# Pyros.net
KiCad netlist of a schematic drawn in Altium Designer
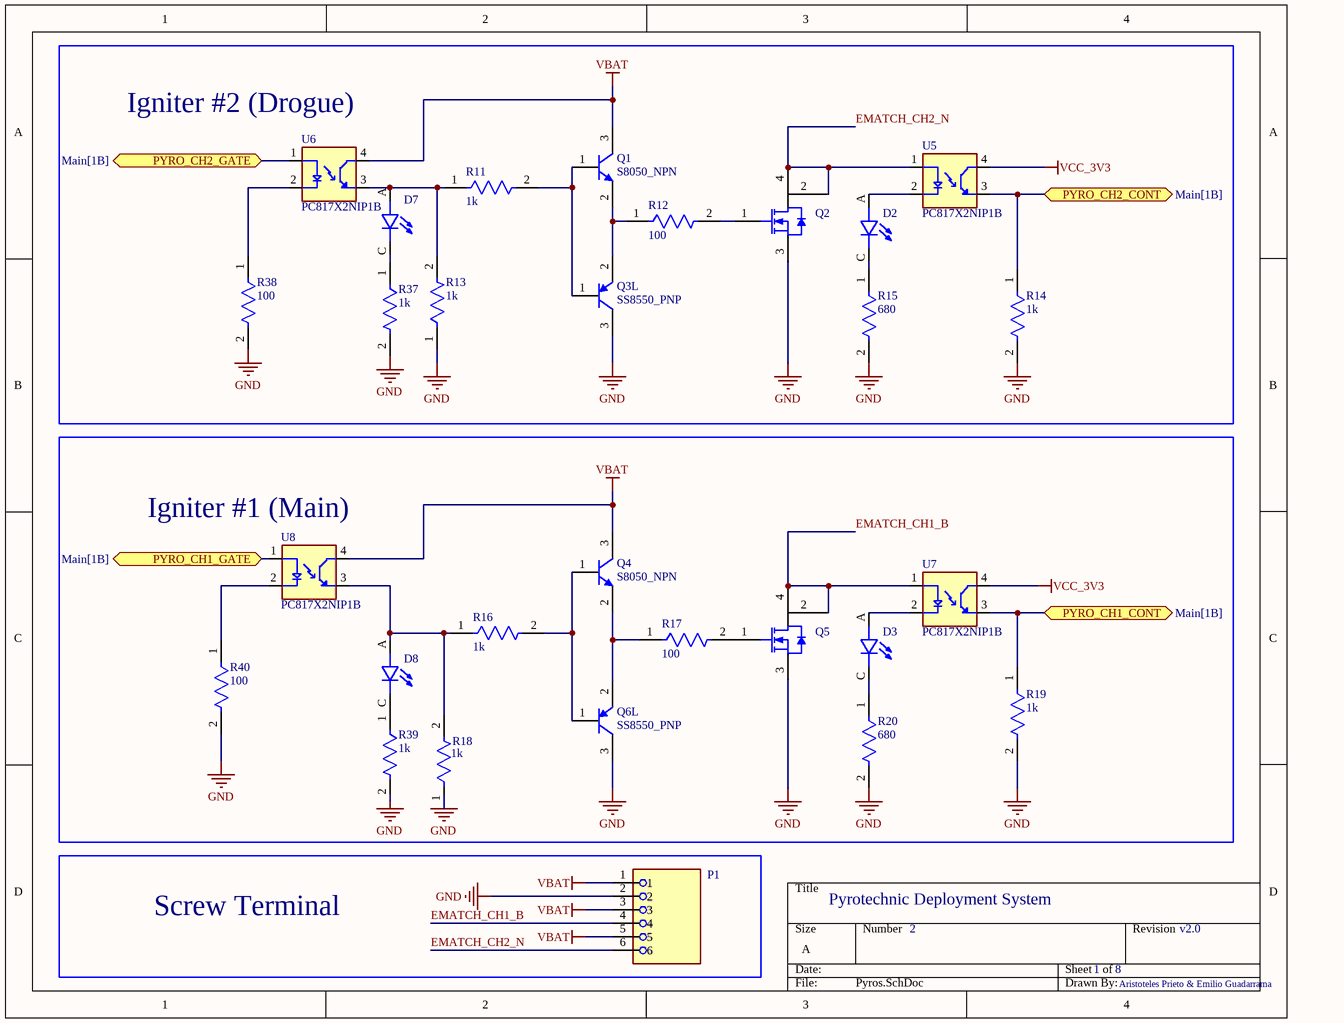
[diagram p0: Pyros.SchDoc]

(export (version "E")
  (design (tool "Eeschema 10.0.6"))
  (components
    (comp (ref "D2")
      (value "SML-LXT0805IW-TR")
      (footprint "LEDC2012X120N")
      (fields (field (name "MF") "Lumex Opto/Components"))
      (libsource (lib "LED_0805-SML-LXT0805IW-TR") (part "SML-LXT0805IW-TR"))
    )
    (comp (ref "D3")
      (value "SML-LXT0805IW-TR")
      (footprint "LEDC2012X120N")
      (fields (field (name "MF") "Lumex Opto/Components"))
      (libsource (lib "LED_0805-SML-LXT0805IW-TR") (part "SML-LXT0805IW-TR"))
    )
    (comp (ref "D7")
      (value "SML-LXT0805IW-TR")
      (footprint "LEDC2012X120N")
      (fields (field (name "MF") "Lumex Opto/Components"))
      (libsource (lib "LED_0805-SML-LXT0805IW-TR") (part "SML-LXT0805IW-TR"))
    )
    (comp (ref "D8")
      (value "SML-LXT0805IW-TR")
      (footprint "LEDC2012X120N")
      (fields (field (name "MF") "Lumex Opto/Components"))
      (libsource (lib "LED_0805-SML-LXT0805IW-TR") (part "SML-LXT0805IW-TR"))
    )
    (comp (ref "P1")
      (value "1729160")
      (footprint "PHOENIX_1729160")
      (fields (field (name "MF") "Phoenix Contact"))
      (libsource (lib "Terminal Screw 5.08mm (6 pin)") (part "1729160"))
    )
    (comp (ref "Q1")
      (value "S8050_NPN")
      (footprint "PCBComponent_1")
      (libsource (lib "NPN_8050") (part "Component_1"))
    )
    (comp (ref "Q2")
      (value "NCE6005AR_Mosfet_N")
      (footprint "PCBComponent_1")
      (libsource (lib "NCE6005AR_Mosfet_N") (part "NCE6005AR"))
    )
    (comp (ref "Q3")
      (value "SS8550_PNP")
      (footprint "PCBComponent_1")
      (libsource (lib "SS8550_PNP") (part "Component_1"))
    )
    (comp (ref "Q4")
      (value "S8050_NPN")
      (footprint "PCBComponent_1")
      (libsource (lib "NPN_8050") (part "Component_1"))
    )
    (comp (ref "Q5")
      (value "NCE6005AR_Mosfet_N")
      (footprint "PCBComponent_1")
      (libsource (lib "NCE6005AR_Mosfet_N") (part "NCE6005AR"))
    )
    (comp (ref "Q6")
      (value "SS8550_PNP")
      (footprint "PCBComponent_1")
      (libsource (lib "SS8550_PNP") (part "Component_1"))
    )
    (comp (ref "R11")
      (value "1k")
      (footprint "FP-MCT0603-IPC_A")
      (description "RES SMD 100 OHM 1% 1/8W 0603")
      (fields (field (name "TOLERANCE") "0.1%"))
      (libsource (lib "Altium Content Vault") (part "1029c3af85768c4190bb7ad29bc67b5"))
    )
    (comp (ref "R12")
      (value "100")
      (footprint "FP-MCT0603-IPC_A")
      (description "RES SMD 100 OHM 1% 1/8W 0603")
      (fields (field (name "TOLERANCE") "0.1%"))
      (libsource (lib "Altium Content Vault") (part "1029c3af85768c4190bb7ad29bc67b5"))
    )
    (comp (ref "R13")
      (value "1k")
      (footprint "FP-MCT0603-IPC_A")
      (description "RES SMD 100 OHM 1% 1/8W 0603")
      (fields (field (name "TOLERANCE") "0.1%"))
      (libsource (lib "Altium Content Vault") (part "1029c3af85768c4190bb7ad29bc67b5"))
    )
    (comp (ref "R14")
      (value "1k")
      (footprint "FP-MCT0603-IPC_A")
      (description "RES SMD 100 OHM 1% 1/8W 0603")
      (fields (field (name "TOLERANCE") "0.1%"))
      (libsource (lib "Altium Content Vault") (part "1029c3af85768c4190bb7ad29bc67b5"))
    )
    (comp (ref "R15")
      (value "680")
      (footprint "FP-MCT0603-IPC_A")
      (description "RES SMD 100 OHM 1% 1/8W 0603")
      (fields (field (name "TOLERANCE") "0.1%"))
      (libsource (lib "Altium Content Vault") (part "1029c3af85768c4190bb7ad29bc67b5"))
    )
    (comp (ref "R16")
      (value "1k")
      (footprint "FP-MCT0603-IPC_A")
      (description "RES SMD 100 OHM 1% 1/8W 0603")
      (fields (field (name "TOLERANCE") "0.1%"))
      (libsource (lib "Altium Content Vault") (part "1029c3af85768c4190bb7ad29bc67b5"))
    )
    (comp (ref "R17")
      (value "100")
      (footprint "FP-MCT0603-IPC_A")
      (description "RES SMD 100 OHM 1% 1/8W 0603")
      (fields (field (name "TOLERANCE") "0.1%"))
      (libsource (lib "Altium Content Vault") (part "1029c3af85768c4190bb7ad29bc67b5"))
    )
    (comp (ref "R18")
      (value "1k")
      (footprint "FP-MCT0603-IPC_A")
      (description "RES SMD 100 OHM 1% 1/8W 0603")
      (fields (field (name "TOLERANCE") "0.1%"))
      (libsource (lib "Altium Content Vault") (part "1029c3af85768c4190bb7ad29bc67b5"))
    )
    (comp (ref "R19")
      (value "1k")
      (footprint "FP-MCT0603-IPC_A")
      (description "RES SMD 100 OHM 1% 1/8W 0603")
      (fields (field (name "TOLERANCE") "0.1%"))
      (libsource (lib "Altium Content Vault") (part "1029c3af85768c4190bb7ad29bc67b5"))
    )
    (comp (ref "R20")
      (value "680")
      (footprint "FP-MCT0603-IPC_A")
      (description "RES SMD 100 OHM 1% 1/8W 0603")
      (fields (field (name "TOLERANCE") "0.1%"))
      (libsource (lib "Altium Content Vault") (part "1029c3af85768c4190bb7ad29bc67b5"))
    )
    (comp (ref "R37")
      (value "1k")
      (footprint "FP-MCT0603-IPC_A")
      (description "RES SMD 100 OHM 1% 1/8W 0603")
      (fields (field (name "TOLERANCE") "0.1%"))
      (libsource (lib "Altium Content Vault") (part "1029c3af85768c4190bb7ad29bc67b5"))
    )
    (comp (ref "R38")
      (value "100")
      (footprint "FP-MCT0603-IPC_A")
      (description "RES SMD 100 OHM 1% 1/8W 0603")
      (fields (field (name "TOLERANCE") "0.1%"))
      (libsource (lib "Altium Content Vault") (part "1029c3af85768c4190bb7ad29bc67b5"))
    )
    (comp (ref "R39")
      (value "1k")
      (footprint "FP-MCT0603-IPC_A")
      (description "RES SMD 100 OHM 1% 1/8W 0603")
      (fields (field (name "TOLERANCE") "0.1%"))
      (libsource (lib "Altium Content Vault") (part "1029c3af85768c4190bb7ad29bc67b5"))
    )
    (comp (ref "R40")
      (value "100")
      (footprint "FP-MCT0603-IPC_A")
      (description "RES SMD 100 OHM 1% 1/8W 0603")
      (fields (field (name "TOLERANCE") "0.1%"))
      (libsource (lib "Altium Content Vault") (part "1029c3af85768c4190bb7ad29bc67b5"))
    )
    (comp (ref "U5")
      (value "PC817X2NIP1B")
      (footprint "SOIC254P960X420-4N")
      (description "Optocoupler DC-IN 1-CH Transistor DC-OUT 4-Pin DIP SMD T/R")
      (fields (field (name "MF") "Sharp Microelectronics"))
      (libsource (lib "Optoisolator-PC817X2NIP1B") (part "PC817X2NIP1B"))
    )
    (comp (ref "U6")
      (value "PC817X2NIP1B")
      (footprint "SOIC254P960X420-4N")
      (description "Optocoupler DC-IN 1-CH Transistor DC-OUT 4-Pin DIP SMD T/R")
      (fields (field (name "MF") "Sharp Microelectronics"))
      (libsource (lib "Optoisolator-PC817X2NIP1B") (part "PC817X2NIP1B"))
    )
    (comp (ref "U7")
      (value "PC817X2NIP1B")
      (footprint "SOIC254P960X420-4N")
      (description "Optocoupler DC-IN 1-CH Transistor DC-OUT 4-Pin DIP SMD T/R")
      (fields (field (name "MF") "Sharp Microelectronics"))
      (libsource (lib "Optoisolator-PC817X2NIP1B") (part "PC817X2NIP1B"))
    )
    (comp (ref "U8")
      (value "PC817X2NIP1B")
      (footprint "SOIC254P960X420-4N")
      (description "Optocoupler DC-IN 1-CH Transistor DC-OUT 4-Pin DIP SMD T/R")
      (fields (field (name "MF") "Sharp Microelectronics"))
      (libsource (lib "Optoisolator-PC817X2NIP1B") (part "PC817X2NIP1B"))
    )
  )
  (nets
    (net (code "1") (name "/EMATCH_CH1_B") (class "Default")
      (node (ref "P1") (pin "4") (pinfunction "4_4") (pintype "passive"))
      (node (ref "Q5") (pin "2") (pinfunction "D_2") (pintype "passive"))
      (node (ref "Q5") (pin "4") (pinfunction "D_4") (pintype "passive"))
      (node (ref "U7") (pin "1") (pinfunction "A_1") (pintype "passive"))
    )
    (net (code "2") (name "/EMATCH_CH2_N") (class "Default")
      (node (ref "P1") (pin "6") (pinfunction "6_6") (pintype "passive"))
      (node (ref "Q2") (pin "2") (pinfunction "D_2") (pintype "passive"))
      (node (ref "Q2") (pin "4") (pinfunction "D_4") (pintype "passive"))
      (node (ref "U5") (pin "1") (pinfunction "A_1") (pintype "passive"))
    )
    (net (code "3") (name "/PYRO_CH1_CONT") (class "Default")
      (node (ref "R19") (pin "1") (pinfunction "1_1") (pintype "passive"))
      (node (ref "U7") (pin "3") (pinfunction "ET_3") (pintype "passive"))
    )
    (net (code "4") (name "/PYRO_CH1_GATE") (class "Default")
      (node (ref "U8") (pin "1") (pinfunction "A_1") (pintype "passive"))
    )
    (net (code "5") (name "/PYRO_CH2_CONT") (class "Default")
      (node (ref "R14") (pin "1") (pinfunction "1_1") (pintype "passive"))
      (node (ref "U5") (pin "3") (pinfunction "ET_3") (pintype "passive"))
    )
    (net (code "6") (name "/PYRO_CH2_GATE") (class "Default")
      (node (ref "U6") (pin "1") (pinfunction "A_1") (pintype "passive"))
    )
    (net (code "7") (name "GND") (class "Default")
      (node (ref "P1") (pin "2") (pinfunction "2_2") (pintype "passive"))
      (node (ref "Q2") (pin "3") (pinfunction "S_3") (pintype "passive"))
      (node (ref "Q3") (pin "3") (pinfunction "C_3") (pintype "passive"))
      (node (ref "Q5") (pin "3") (pinfunction "S_3") (pintype "passive"))
      (node (ref "Q6") (pin "3") (pinfunction "C_3") (pintype "passive"))
      (node (ref "R13") (pin "1") (pinfunction "1_1") (pintype "passive"))
      (node (ref "R14") (pin "2") (pinfunction "2_2") (pintype "passive"))
      (node (ref "R15") (pin "2") (pinfunction "2_2") (pintype "passive"))
      (node (ref "R18") (pin "1") (pinfunction "1_1") (pintype "passive"))
      (node (ref "R19") (pin "2") (pinfunction "2_2") (pintype "passive"))
      (node (ref "R20") (pin "2") (pinfunction "2_2") (pintype "passive"))
      (node (ref "R37") (pin "2") (pinfunction "2_2") (pintype "passive"))
      (node (ref "R38") (pin "2") (pinfunction "2_2") (pintype "passive"))
      (node (ref "R39") (pin "2") (pinfunction "2_2") (pintype "passive"))
      (node (ref "R40") (pin "2") (pinfunction "2_2") (pintype "passive"))
    )
    (net (code "8") (name "Net-(D2-PadC)") (class "Default")
      (node (ref "D2") (pin "C") (pinfunction "C_C") (pintype "passive"))
      (node (ref "R15") (pin "1") (pinfunction "1_1") (pintype "passive"))
    )
    (net (code "9") (name "Net-(D3-PadC)") (class "Default")
      (node (ref "D3") (pin "C") (pinfunction "C_C") (pintype "passive"))
      (node (ref "R20") (pin "1") (pinfunction "1_1") (pintype "passive"))
    )
    (net (code "10") (name "Net-(D7-PadC)") (class "Default")
      (node (ref "D7") (pin "C") (pinfunction "C_C") (pintype "passive"))
      (node (ref "R37") (pin "1") (pinfunction "1_1") (pintype "passive"))
    )
    (net (code "11") (name "Net-(D8-PadC)") (class "Default")
      (node (ref "D8") (pin "C") (pinfunction "C_C") (pintype "passive"))
      (node (ref "R39") (pin "1") (pinfunction "1_1") (pintype "passive"))
    )
    (net (code "12") (name "Net-(Q1-B)") (class "Default")
      (node (ref "Q1") (pin "1") (pinfunction "B_1") (pintype "passive"))
      (node (ref "Q3") (pin "1") (pinfunction "B_1") (pintype "passive"))
      (node (ref "R11") (pin "2") (pinfunction "2_2") (pintype "passive"))
    )
    (net (code "13") (name "Net-(Q1-E)") (class "Default")
      (node (ref "Q1") (pin "2") (pinfunction "E_2") (pintype "passive"))
      (node (ref "Q3") (pin "2") (pinfunction "E_2") (pintype "passive"))
      (node (ref "R12") (pin "1") (pinfunction "1_1") (pintype "passive"))
    )
    (net (code "14") (name "Net-(Q2-G)") (class "Default")
      (node (ref "Q2") (pin "1") (pinfunction "G_1") (pintype "passive"))
      (node (ref "R12") (pin "2") (pinfunction "2_2") (pintype "passive"))
    )
    (net (code "15") (name "Net-(Q4-B)") (class "Default")
      (node (ref "Q4") (pin "1") (pinfunction "B_1") (pintype "passive"))
      (node (ref "Q6") (pin "1") (pinfunction "B_1") (pintype "passive"))
      (node (ref "R16") (pin "2") (pinfunction "2_2") (pintype "passive"))
    )
    (net (code "16") (name "Net-(Q4-E)") (class "Default")
      (node (ref "Q4") (pin "2") (pinfunction "E_2") (pintype "passive"))
      (node (ref "Q6") (pin "2") (pinfunction "E_2") (pintype "passive"))
      (node (ref "R17") (pin "1") (pinfunction "1_1") (pintype "passive"))
    )
    (net (code "17") (name "Net-(Q5-G)") (class "Default")
      (node (ref "Q5") (pin "1") (pinfunction "G_1") (pintype "passive"))
      (node (ref "R17") (pin "2") (pinfunction "2_2") (pintype "passive"))
    )
    (net (code "18") (name "Net-(U5-C)") (class "Default")
      (node (ref "D2") (pin "A") (pinfunction "A_A") (pintype "passive"))
      (node (ref "U5") (pin "2") (pinfunction "C_2") (pintype "passive"))
    )
    (net (code "19") (name "Net-(U6-C)") (class "Default")
      (node (ref "R38") (pin "1") (pinfunction "1_1") (pintype "passive"))
      (node (ref "U6") (pin "2") (pinfunction "C_2") (pintype "passive"))
    )
    (net (code "20") (name "Net-(U6-ET)") (class "Default")
      (node (ref "D7") (pin "A") (pinfunction "A_A") (pintype "passive"))
      (node (ref "R11") (pin "1") (pinfunction "1_1") (pintype "passive"))
      (node (ref "R13") (pin "2") (pinfunction "2_2") (pintype "passive"))
      (node (ref "U6") (pin "3") (pinfunction "ET_3") (pintype "passive"))
    )
    (net (code "21") (name "Net-(U7-C)") (class "Default")
      (node (ref "D3") (pin "A") (pinfunction "A_A") (pintype "passive"))
      (node (ref "U7") (pin "2") (pinfunction "C_2") (pintype "passive"))
    )
    (net (code "22") (name "Net-(U8-C)") (class "Default")
      (node (ref "R40") (pin "1") (pinfunction "1_1") (pintype "passive"))
      (node (ref "U8") (pin "2") (pinfunction "C_2") (pintype "passive"))
    )
    (net (code "23") (name "Net-(U8-ET)") (class "Default")
      (node (ref "D8") (pin "A") (pinfunction "A_A") (pintype "passive"))
      (node (ref "R16") (pin "1") (pinfunction "1_1") (pintype "passive"))
      (node (ref "R18") (pin "2") (pinfunction "2_2") (pintype "passive"))
      (node (ref "U8") (pin "3") (pinfunction "ET_3") (pintype "passive"))
    )
    (net (code "24") (name "VBAT") (class "Default")
      (node (ref "P1") (pin "1") (pinfunction "1_1") (pintype "passive"))
      (node (ref "P1") (pin "3") (pinfunction "3_3") (pintype "passive"))
      (node (ref "P1") (pin "5") (pinfunction "5_5") (pintype "passive"))
      (node (ref "Q1") (pin "3") (pinfunction "C_3") (pintype "passive"))
      (node (ref "Q4") (pin "3") (pinfunction "C_3") (pintype "passive"))
      (node (ref "U6") (pin "4") (pinfunction "CT_4") (pintype "passive"))
      (node (ref "U8") (pin "4") (pinfunction "CT_4") (pintype "passive"))
    )
    (net (code "25") (name "VCC_3V3") (class "Default")
      (node (ref "U5") (pin "4") (pinfunction "CT_4") (pintype "passive"))
      (node (ref "U7") (pin "4") (pinfunction "CT_4") (pintype "passive"))
    )
  )
)
